# Digital-WeighingScale.net
KiCad netlist of a schematic drawn in Altium Designer
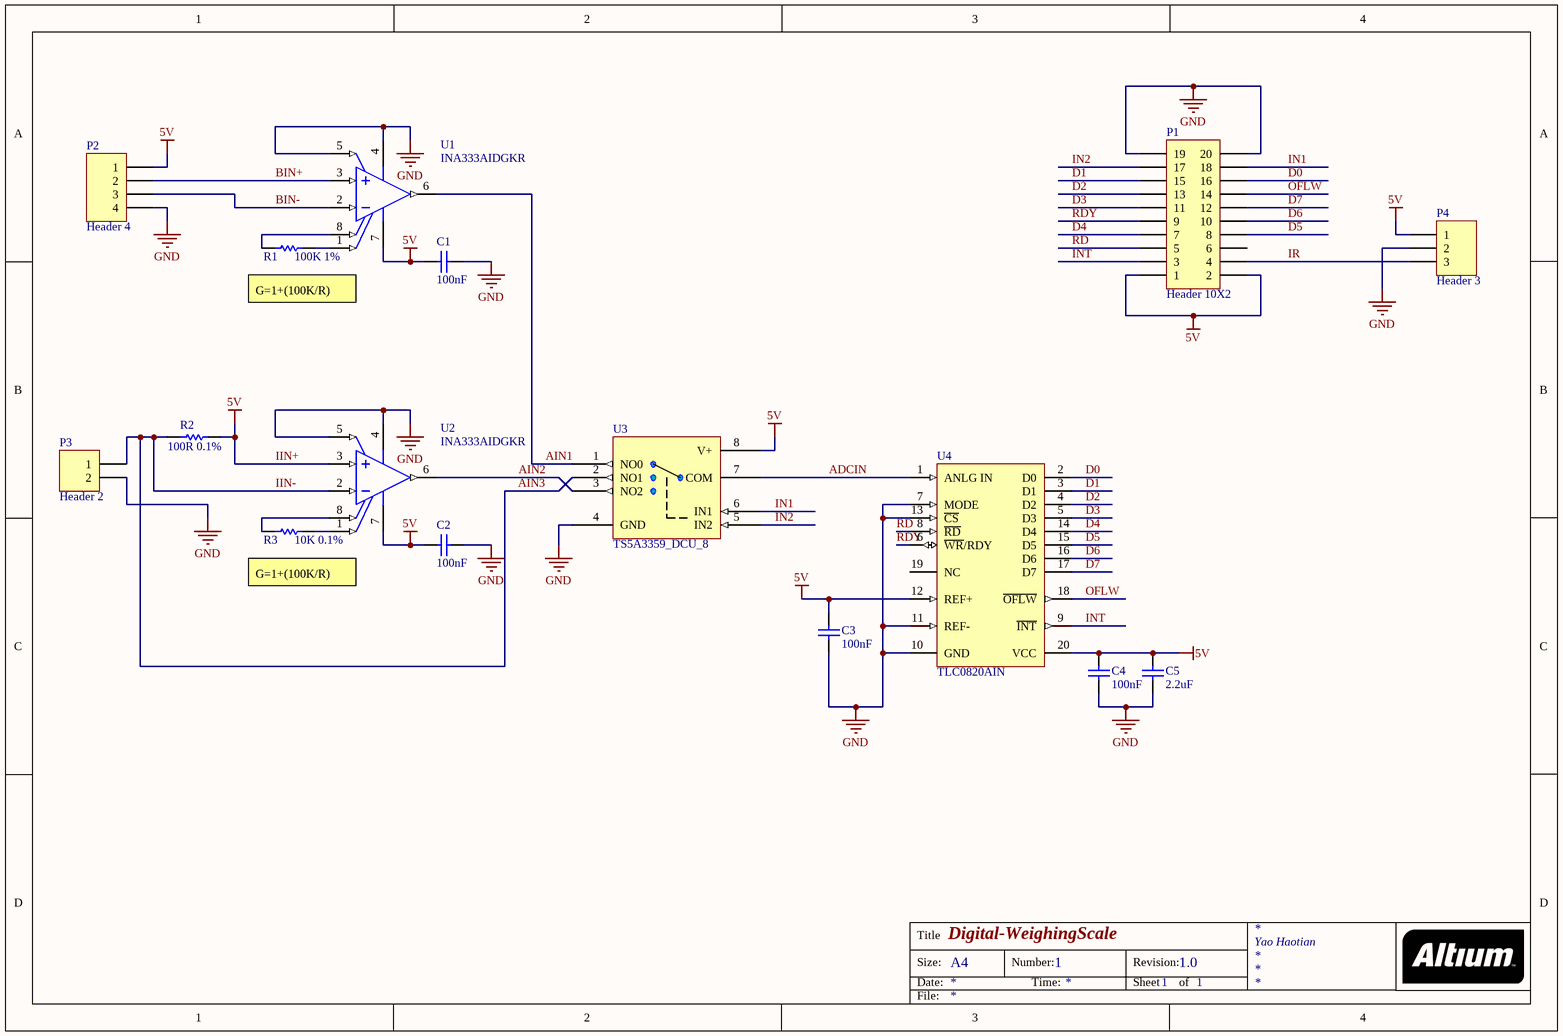
[diagram p0: Digital-WeighingScale.SchDoc]

(export (version "E")
  (design (tool "Eeschema 10.0.6"))
  (components
    (comp (ref "C1")
      (value "100nF")
      (footprint "CAPC0603(1608)100_M")
      (description "CAP 100nF 16V Â±5% 0603 (1608 Metric) Thickness 1mm SMD")
      (fields (field (name "TOLERANCE") "Â±5%"))
      (libsource (lib "Altium Content Vault") (part "CMP-1035-02583-1"))
    )
    (comp (ref "C2")
      (value "100nF")
      (footprint "CAPC0603(1608)100_M")
      (description "CAP 100nF 16V Â±5% 0603 (1608 Metric) Thickness 1mm SMD")
      (fields (field (name "TOLERANCE") "Â±5%"))
      (libsource (lib "Altium Content Vault") (part "CMP-1035-02583-1"))
    )
    (comp (ref "C3")
      (value "100nF")
      (footprint "CAPC0603(1608)100_M")
      (description "CAP 100nF 16V Â±5% 0603 (1608 Metric) Thickness 1mm SMD")
      (fields (field (name "TOLERANCE") "Â±5%"))
      (libsource (lib "Altium Content Vault") (part "CMP-1035-02583-1"))
    )
    (comp (ref "C4")
      (value "100nF")
      (footprint "CAPC0603(1608)100_M")
      (description "CAP 100nF 16V Â±5% 0603 (1608 Metric) Thickness 1mm SMD")
      (fields (field (name "TOLERANCE") "Â±5%"))
      (libsource (lib "Altium Content Vault") (part "CMP-1035-02583-1"))
    )
    (comp (ref "C5")
      (value "2.2uF")
      (footprint "CAPC0603(1608)100_M")
      (description "CAP 2.2uF 16V Â±5% 0603 (1608 Metric) Thickness 1mm SMD")
      (fields (field (name "TOLERANCE") "Â±5%"))
      (libsource (lib "Altium Content Vault") (part "CMP-1035-02583-1"))
    )
    (comp (ref "P1")
      (value "Header 10X2")
      (footprint "HDR2X10")
      (description "Header, 10-Pin, Dual row")
      (fields (field (name "PUBLISHER") "Altium Limited"))
      (libsource (lib "Miscellaneous Connectors") (part "Header 10X2"))
    )
    (comp (ref "P2")
      (value "Header 4")
      (footprint "HDR1X4")
      (description "Header, 4-Pin")
      (fields (field (name "PUBLISHER") "Altium Limited"))
      (libsource (lib "Miscellaneous Connectors") (part "Header 4"))
    )
    (comp (ref "P3")
      (value "Header 2")
      (footprint "HDR1X2")
      (description "Header, 2-Pin")
      (fields (field (name "PUBLISHER") "Altium Limited"))
      (libsource (lib "Miscellaneous Connectors") (part "Header 2"))
    )
    (comp (ref "P4")
      (value "Header 3")
      (footprint "HDR1X3")
      (description "Header, 3-Pin")
      (fields (field (name "PUBLISHER") "Altium Limited"))
      (libsource (lib "Miscellaneous Connectors") (part "Header 3"))
    )
    (comp (ref "R1")
      (value "100K 1%")
      (footprint "RESC0603(1608)_M")
      (description "100K 0.1W 1% 0603 (1608 Metric)  SMD")
      (fields (field (name "POWER") "0.1 W") (field (name "TOLERANCE") "1 %"))
      (libsource (lib "Altium Content Vault") (part "CMP-1012-00736-1"))
    )
    (comp (ref "R2")
      (value "100R 0.1%")
      (footprint "RESC0603(1608)_M")
      (description "1K 0.1W 1% 0603 (1608 Metric)  SMD")
      (fields (field (name "TOLERANCE") "0.1 %") (field (name "POWER") "0.1 W"))
      (libsource (lib "Altium Content Vault") (part "CMP-1012-00510-1"))
    )
    (comp (ref "R3")
      (value "10K 0.1%")
      (footprint "RESC0603(1608)_M")
      (description "100K 0.1W 1% 0603 (1608 Metric)  SMD")
      (fields (field (name "POWER") "0.1 W") (field (name "TOLERANCE") "1 %"))
      (libsource (lib "Altium Content Vault") (part "CMP-1012-00736-1"))
    )
    (comp (ref "U1")
      (value "INA333AIDGKR")
      (footprint "TI-DGK8_L")
      (fields (field (name "MANUFACTURER") "Texas Instruments"))
      (libsource (lib "Altium Content Vault") (part "TI-INAXXXXXX8"))
    )
    (comp (ref "U2")
      (value "INA333AIDGKR")
      (footprint "TI-DGK8_L")
      (fields (field (name "MANUFACTURER") "Texas Instruments"))
      (libsource (lib "Altium Content Vault") (part "TI-INAXXXXXX8"))
    )
    (comp (ref "U3")
      (value "TS5A3359_DCU_8")
      (footprint "DCU8-M")
      (description "Imported")
      (fields
        (field (name "MANUFACTURER_PART_NUMBER") "ts5a3359_dcu_8")
        (field (name "GENERIC_PART_NUMBER") "TS5A3359")
      )
      (libsource (lib "Schlib") (part "TS5A3359_DCU_8"))
    )
    (comp (ref "U4")
      (value "TLC0820AIN")
      (footprint "TI-N20")
      (fields (field (name "MANUFACTURER") "Texas Instruments"))
      (libsource (lib "Altium Content Vault") (part "TI-TLC0820A-20"))
    )
  )
  (nets
    (net (code "1") (name "/ADCIN") (class "Default")
      (node (ref "U3") (pin "7") (pinfunction "COM_7") (pintype "passive"))
      (node (ref "U4") (pin "1") (pinfunction "ANLG_IN_1") (pintype "input"))
    )
    (net (code "2") (name "/AIN1") (class "Default")
      (node (ref "U1") (pin "6") (pinfunction "VOUT_6") (pintype "output"))
      (node (ref "U3") (pin "1") (pinfunction "NO0_1") (pintype "output"))
    )
    (net (code "3") (name "/AIN2") (class "Default")
      (node (ref "U2") (pin "6") (pinfunction "VOUT_6") (pintype "output"))
      (node (ref "U3") (pin "3") (pinfunction "NO2_3") (pintype "output"))
    )
    (net (code "4") (name "/AIN3") (class "Default")
      (node (ref "P3") (pin "1") (pinfunction "1_1") (pintype "passive"))
      (node (ref "R2") (pin "1") (pinfunction "1_1") (pintype "passive"))
      (node (ref "U2") (pin "2") (pinfunction "VIN-_2") (pintype "input"))
      (node (ref "U3") (pin "2") (pinfunction "NO1_2") (pintype "output"))
    )
    (net (code "5") (name "/BIN+") (class "Default")
      (node (ref "P2") (pin "2") (pinfunction "2_2") (pintype "passive"))
      (node (ref "U1") (pin "3") (pinfunction "VIN+_3") (pintype "input"))
    )
    (net (code "6") (name "/BIN-") (class "Default")
      (node (ref "P2") (pin "3") (pinfunction "3_3") (pintype "passive"))
      (node (ref "U1") (pin "2") (pinfunction "VIN-_2") (pintype "input"))
    )
    (net (code "7") (name "/D0") (class "Default")
      (node (ref "P1") (pin "16") (pinfunction "16_16") (pintype "passive"))
      (node (ref "U4") (pin "2") (pinfunction "D0_2") (pintype "tri_state"))
    )
    (net (code "8") (name "/D1") (class "Default")
      (node (ref "P1") (pin "15") (pinfunction "15_15") (pintype "passive"))
      (node (ref "U4") (pin "3") (pinfunction "D1_3") (pintype "tri_state"))
    )
    (net (code "9") (name "/D2") (class "Default")
      (node (ref "P1") (pin "13") (pinfunction "13_13") (pintype "passive"))
      (node (ref "U4") (pin "4") (pinfunction "D2_4") (pintype "tri_state"))
    )
    (net (code "10") (name "/D3") (class "Default")
      (node (ref "P1") (pin "11") (pinfunction "11_11") (pintype "passive"))
      (node (ref "U4") (pin "5") (pinfunction "D3_5") (pintype "tri_state"))
    )
    (net (code "11") (name "/D4") (class "Default")
      (node (ref "P1") (pin "7") (pinfunction "7_7") (pintype "passive"))
      (node (ref "U4") (pin "14") (pinfunction "D4_14") (pintype "tri_state"))
    )
    (net (code "12") (name "/D5") (class "Default")
      (node (ref "P1") (pin "8") (pinfunction "8_8") (pintype "passive"))
      (node (ref "U4") (pin "15") (pinfunction "D5_15") (pintype "tri_state"))
    )
    (net (code "13") (name "/D6") (class "Default")
      (node (ref "P1") (pin "10") (pinfunction "10_10") (pintype "passive"))
      (node (ref "U4") (pin "16") (pinfunction "D6_16") (pintype "tri_state"))
    )
    (net (code "14") (name "/D7") (class "Default")
      (node (ref "P1") (pin "12") (pinfunction "12_12") (pintype "passive"))
      (node (ref "U4") (pin "17") (pinfunction "D7_17") (pintype "tri_state"))
    )
    (net (code "15") (name "/IN1") (class "Default")
      (node (ref "P1") (pin "18") (pinfunction "18_18") (pintype "passive"))
      (node (ref "U3") (pin "6") (pinfunction "IN1_6") (pintype "input"))
    )
    (net (code "16") (name "/IN2") (class "Default")
      (node (ref "P1") (pin "17") (pinfunction "17_17") (pintype "passive"))
      (node (ref "U3") (pin "5") (pinfunction "IN2_5") (pintype "input"))
    )
    (net (code "17") (name "/INT") (class "Default")
      (node (ref "P1") (pin "3") (pinfunction "3_3") (pintype "passive"))
      (node (ref "U4") (pin "9") (pinfunction "~{INT}_9") (pintype "output"))
    )
    (net (code "18") (name "/IR") (class "Default")
      (node (ref "P1") (pin "4") (pinfunction "4_4") (pintype "passive"))
      (node (ref "P4") (pin "3") (pinfunction "3_3") (pintype "passive"))
    )
    (net (code "19") (name "/OFLW") (class "Default")
      (node (ref "P1") (pin "14") (pinfunction "14_14") (pintype "passive"))
      (node (ref "U4") (pin "18") (pinfunction "~{OFLW}_18") (pintype "output"))
    )
    (net (code "20") (name "/RD") (class "Default")
      (node (ref "P1") (pin "5") (pinfunction "5_5") (pintype "passive"))
      (node (ref "U4") (pin "8") (pinfunction "~{RD}_8") (pintype "input"))
    )
    (net (code "21") (name "/RDY") (class "Default")
      (node (ref "P1") (pin "9") (pinfunction "9_9") (pintype "passive"))
      (node (ref "U4") (pin "6") (pinfunction "~{WR}/RDY_6") (pintype "bidirectional"))
    )
    (net (code "22") (name "5V") (class "Default")
      (node (ref "C1") (pin "2") (pinfunction "2_2") (pintype "passive"))
      (node (ref "C2") (pin "2") (pinfunction "2_2") (pintype "passive"))
      (node (ref "C3") (pin "1") (pinfunction "1_1") (pintype "passive"))
      (node (ref "C4") (pin "1") (pinfunction "1_1") (pintype "passive"))
      (node (ref "C5") (pin "1") (pinfunction "1_1") (pintype "passive"))
      (node (ref "P1") (pin "1") (pinfunction "1_1") (pintype "passive"))
      (node (ref "P1") (pin "2") (pinfunction "2_2") (pintype "passive"))
      (node (ref "P2") (pin "1") (pinfunction "1_1") (pintype "passive"))
      (node (ref "P4") (pin "1") (pinfunction "1_1") (pintype "passive"))
      (node (ref "R2") (pin "2") (pinfunction "2_2") (pintype "passive"))
      (node (ref "U1") (pin "7") (pinfunction "V+_7") (pintype "power_in"))
      (node (ref "U2") (pin "3") (pinfunction "VIN+_3") (pintype "input"))
      (node (ref "U2") (pin "7") (pinfunction "V+_7") (pintype "power_in"))
      (node (ref "U3") (pin "8") (pinfunction "V+_8") (pintype "power_in"))
      (node (ref "U4") (pin "12") (pinfunction "REF+_12") (pintype "input"))
      (node (ref "U4") (pin "20") (pinfunction "VCC_20") (pintype "power_in"))
    )
    (net (code "23") (name "GND") (class "Default")
      (node (ref "C1") (pin "1") (pinfunction "1_1") (pintype "passive"))
      (node (ref "C2") (pin "1") (pinfunction "1_1") (pintype "passive"))
      (node (ref "C3") (pin "2") (pinfunction "2_2") (pintype "passive"))
      (node (ref "C4") (pin "2") (pinfunction "2_2") (pintype "passive"))
      (node (ref "C5") (pin "2") (pinfunction "2_2") (pintype "passive"))
      (node (ref "P1") (pin "19") (pinfunction "19_19") (pintype "passive"))
      (node (ref "P1") (pin "20") (pinfunction "20_20") (pintype "passive"))
      (node (ref "P2") (pin "4") (pinfunction "4_4") (pintype "passive"))
      (node (ref "P3") (pin "2") (pinfunction "2_2") (pintype "passive"))
      (node (ref "P4") (pin "2") (pinfunction "2_2") (pintype "passive"))
      (node (ref "U1") (pin "4") (pinfunction "V-_4") (pintype "power_in"))
      (node (ref "U1") (pin "5") (pinfunction "REF_5") (pintype "input"))
      (node (ref "U2") (pin "4") (pinfunction "V-_4") (pintype "power_in"))
      (node (ref "U2") (pin "5") (pinfunction "REF_5") (pintype "input"))
      (node (ref "U3") (pin "4") (pinfunction "GND_4") (pintype "power_in"))
      (node (ref "U4") (pin "10") (pinfunction "GND_10") (pintype "power_in"))
      (node (ref "U4") (pin "11") (pinfunction "REF-_11") (pintype "input"))
      (node (ref "U4") (pin "13") (pinfunction "~{CS}_13") (pintype "input"))
      (node (ref "U4") (pin "7") (pinfunction "MODE_7") (pintype "input"))
    )
    (net (code "24") (name "Net-(R1-Pad1)") (class "Default")
      (node (ref "R1") (pin "1") (pinfunction "1_1") (pintype "passive"))
      (node (ref "U1") (pin "8") (pinfunction "RG_8") (pintype "input"))
    )
    (net (code "25") (name "Net-(R1-Pad2)") (class "Default")
      (node (ref "R1") (pin "2") (pinfunction "2_2") (pintype "passive"))
      (node (ref "U1") (pin "1") (pinfunction "RG_1") (pintype "input"))
    )
    (net (code "26") (name "Net-(R3-Pad1)") (class "Default")
      (node (ref "R3") (pin "1") (pinfunction "1_1") (pintype "passive"))
      (node (ref "U2") (pin "8") (pinfunction "RG_8") (pintype "input"))
    )
    (net (code "27") (name "Net-(R3-Pad2)") (class "Default")
      (node (ref "R3") (pin "2") (pinfunction "2_2") (pintype "passive"))
      (node (ref "U2") (pin "1") (pinfunction "RG_1") (pintype "input"))
    )
    (net (code "28") (name "unconnected-(P1-Pad6)") (class "Default")
      (node (ref "P1") (pin "6") (pinfunction "6_6") (pintype "passive"))
    )
    (net (code "29") (name "unconnected-(U4-NC-Pad19)") (class "Default")
      (node (ref "U4") (pin "19") (pinfunction "NC_19") (pintype "passive"))
    )
  )
)
